# Supply.net
KiCad netlist of a schematic drawn in Altium Designer
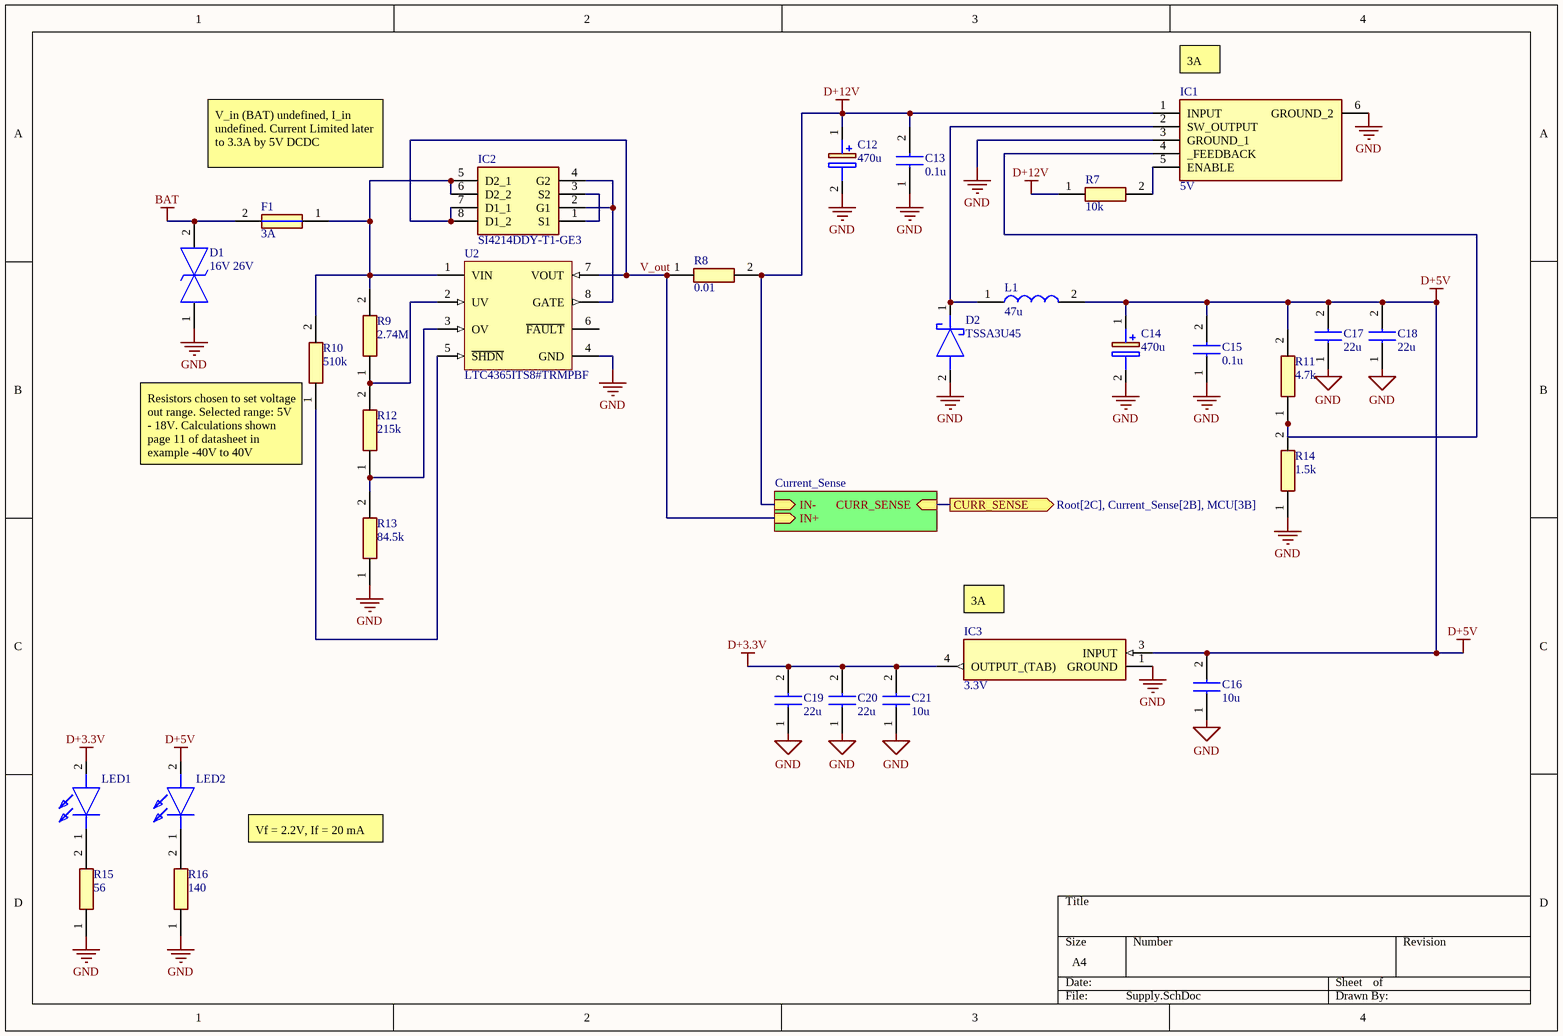
[diagram p0: Supply.SchDoc]

(export (version "E")
  (design (tool "Eeschema 10.0.6"))
  (components
    (comp (ref "C12")
      (value "470u")
      (footprint "SamacSys:CAPAE1030X1080N")
      (description "UWT1E471MNL1GS")
      (fields (field (name "MOUSER PART NUMBER") "647-UWT1E471MNL1S"))
      (libsource (lib "*") (part "UWT1E471MNL1GS"))
    )
    (comp (ref "C13")
      (value "0.1u")
      (footprint "SamacSys:CAPC1608X90N")
      (description "CC0603KRX7R8BB104")
      (fields (field (name "MOUSER PART NUMBER") "603-CC603KRX7R8BB104"))
      (libsource (lib "*") (part "CC0603KRX7R8BB104"))
    )
    (comp (ref "C14")
      (value "470u")
      (footprint "SamacSys:CAPAE1030X1080N")
      (description "UWT1E471MNL1GS")
      (fields (field (name "MOUSER PART NUMBER") "647-UWT1E471MNL1S"))
      (libsource (lib "*") (part "UWT1E471MNL1GS"))
    )
    (comp (ref "C15")
      (value "0.1u")
      (footprint "SamacSys:CAPC1608X90N")
      (description "CC0603KRX7R8BB104")
      (fields (field (name "MOUSER PART NUMBER") "603-CC603KRX7R8BB104"))
      (libsource (lib "*") (part "CC0603KRX7R8BB104"))
    )
    (comp (ref "C16")
      (value "10u")
      (footprint "SamacSys:GRM18x")
      (description "GRM188R61A106ME69D")
      (fields (field (name "MOUSER PART NUMBER") "81-GRM188R61A106ME9D"))
      (libsource (lib "*") (part "GRM188R61A106ME69D"))
    )
    (comp (ref "C17")
      (value "22u")
      (footprint "SamacSys:CAPC2012X95N")
      (description "GRM219R61A226MEA0D")
      (fields (field (name "MOUSER PART NUMBER") "81-GRM219R61A226ME0D"))
      (libsource (lib "*") (part "GRM219R61A226MEA0D"))
    )
    (comp (ref "C18")
      (value "22u")
      (footprint "SamacSys:CAPC2012X95N")
      (description "GRM219R61A226MEA0D")
      (fields (field (name "MOUSER PART NUMBER") "81-GRM219R61A226ME0D"))
      (libsource (lib "*") (part "GRM219R61A226MEA0D"))
    )
    (comp (ref "C19")
      (value "22u")
      (footprint "SamacSys:CAPC2012X95N")
      (description "GRM219R61A226MEA0D")
      (fields (field (name "MOUSER PART NUMBER") "81-GRM219R61A226ME0D"))
      (libsource (lib "*") (part "GRM219R61A226MEA0D"))
    )
    (comp (ref "C20")
      (value "22u")
      (footprint "SamacSys:CAPC2012X95N")
      (description "GRM219R61A226MEA0D")
      (fields (field (name "MOUSER PART NUMBER") "81-GRM219R61A226ME0D"))
      (libsource (lib "*") (part "GRM219R61A226MEA0D"))
    )
    (comp (ref "C21")
      (value "10u")
      (footprint "SamacSys:GRM18x")
      (description "GRM188R61A106ME69D")
      (fields (field (name "MOUSER PART NUMBER") "81-GRM188R61A106ME9D"))
      (libsource (lib "*") (part "GRM188R61A106ME69D"))
    )
    (comp (ref "D1")
      (value "16V 26V")
      (footprint "SamacSys:DIONM5226X240N")
      (description "SMAJ16CA-13-F")
      (fields (field (name "MOUSER PART NUMBER") "621-SMAJ16CA-13-F"))
      (libsource (lib "*") (part "SMAJ16CA-13-F"))
    )
    (comp (ref "D2")
      (value "TSSA3U45")
      (footprint "SamacSys:DIOM5126X250N")
      (description "Schottky Diode")
      (fields (field (name "MOUSER PART NUMBER") "821-TSSA3U45"))
      (libsource (lib "*") (part "TSSA3U45"))
    )
    (comp (ref "F1")
      (value "3A")
      (footprint "SamacSys:FUSC3216X83N")
      (description "0685T3000-01")
      (libsource (lib "*") (part "0685T3000-01"))
    )
    (comp (ref "IC1")
      (value "5V")
      (footprint "SamacSys:TS2596CM550RNG")
      (description "TS2596CM550_RNG")
      (fields
        (field (name "MANUFACTURER_PART_NUMBER") "TS2596CM550 RNG")
        (field (name "MOUSER PART NUMBER") "821-TS2596CM550RNG")
      )
      (libsource (lib "*") (part "TS2596CM550_RNG"))
    )
    (comp (ref "IC2")
      (value "SI4214DDY-T1-GE3")
      (footprint "SamacSys:SOIC127P600X175-8N")
      (description "Integrated Circuit")
      (fields (field (name "MOUSER PART NUMBER") "781-SI4214DDY-GE3"))
      (libsource (lib "*") (part "SI4214DDY-T1-GE3"))
    )
    (comp (ref "IC3")
      (value "3.3V")
      (footprint "SamacSys:TO254P1542X460-3N")
      (description "LD1085D2M33R")
      (fields (field (name "MOUSER PART NUMBER") "511-LD1085D2M33-TR"))
      (libsource (lib "*") (part "LD1085D2M33R"))
    )
    (comp (ref "L1")
      (value "47u")
      (footprint "SamacSys:104CDMCCDS470MC")
      (description "104CDMCCDS-470MC")
      (fields (field (name "MOUSER PART NUMBER") "851-104CDMCCDS-470MC"))
      (libsource (lib "*") (part "104CDMCCDS-470MC"))
    )
    (comp (ref "LED1")
      (value "SML-D12P8WT86C")
      (footprint "SamacSys:LEDM1620X150N")
      (description "LED")
      (fields (field (name "MOUSER PART NUMBER") "755-SML-D12P8WT86C"))
      (libsource (lib "*") (part "SML-D12P8WT86C"))
    )
    (comp (ref "LED2")
      (value "SML-D12P8WT86C")
      (footprint "SamacSys:LEDM1620X150N")
      (description "LED")
      (fields (field (name "MOUSER PART NUMBER") "755-SML-D12P8WT86C"))
      (libsource (lib "*") (part "SML-D12P8WT86C"))
    )
    (comp (ref "R7")
      (value "10k")
      (footprint "SamacSys:RESC1608X55N")
      (description "RC0603FR0710KL")
      (libsource (lib "*") (part "RC0603FR0710KL"))
    )
    (comp (ref "R8")
      (value "0.01")
      (footprint "SamacSys:CSS0603FT10L0")
      (description "CSS0603FT10L0")
      (fields (field (name "MOUSER PART NUMBER") "708-CSS0603FT10L0"))
      (libsource (lib "*") (part "CSS0603FT10L0"))
    )
    (comp (ref "R9")
      (value "2.74M")
      (footprint "SamacSys:RESC1608X50N")
      (description "CRCW06032M74FKEA")
      (fields (field (name "MOUSER PART NUMBER") "71-CRCW0603-2.74M-E3"))
      (libsource (lib "*") (part "CRCW06032M74FKEA"))
    )
    (comp (ref "R10")
      (value "510k")
      (footprint "SamacSys:RESC1608X55N")
      (description "RC0603JR-07510KL")
      (fields (field (name "MOUSER PART NUMBER") "603-RC0603JR-07510KL"))
      (libsource (lib "*") (part "RC0603JR-07510KL"))
    )
    (comp (ref "R11")
      (value "4.7k")
      (footprint "SamacSys:RESC1608X55N")
      (description "RC0603FR-074K7L")
      (fields (field (name "MOUSER PART NUMBER") "603-RC0603FR-074K7L"))
      (libsource (lib "*") (part "RC0603FR-074K7L"))
    )
    (comp (ref "R12")
      (value "215k")
      (footprint "SamacSys:RESC1608X55N")
      (description "ERJ-3EKF2153V")
      (fields (field (name "MOUSER PART NUMBER") "667-ERJ-3EKF2153V"))
      (libsource (lib "*") (part "ERJ-3EKF2153V"))
    )
    (comp (ref "R13")
      (value "84.5k")
      (footprint "SamacSys:RESC1608X55N")
      (description "RC0603FR-0784K5L")
      (fields (field (name "MOUSER PART NUMBER") "603-RC0603FR-0784K5L"))
      (libsource (lib "*") (part "RC0603FR-0784K5L"))
    )
    (comp (ref "R14")
      (value "1.5k")
      (footprint "SamacSys:RESC1608X55N")
      (description "RC0603FR-071K5L")
      (fields (field (name "MOUSER PART NUMBER") "603-RC0603FR-071K5L"))
      (libsource (lib "*") (part "RC0603FR-071K5L"))
    )
    (comp (ref "R15")
      (value "56")
      (footprint "SamacSys:RESC2012X60N")
      (description "RC0805FR-0756RL")
      (fields (field (name "MOUSER PART NUMBER") "603-RC0805FR-0756RL"))
      (libsource (lib "*") (part "RC0805FR-0756RL"))
    )
    (comp (ref "R16")
      (value "140")
      (footprint "SamacSys:RESC2012X60N")
      (description "RC0805FR-07140RL")
      (fields (field (name "MOUSER PART NUMBER") "603-RC0805FR-07140RL"))
      (libsource (lib "*") (part "RC0805FR-07140RL"))
    )
    (comp (ref "U2")
      (value "LTC4365ITS8#TRMPBF")
      (footprint "LT-TS8-8-TSOT-23_V")
      (fields (field (name "MANUFACTURER") "Linear Technology"))
      (libsource (lib "Altium Content Vault") (part "LT-LTC4365-TS8-8"))
    )
  )
  (nets
    (net (code "2") (name "/V_out") (class "Default")
      (node (ref "IC2") (pin "7") (pinfunction "D1_1_7") (pintype "passive"))
      (node (ref "IC2") (pin "8") (pinfunction "D1_2_8") (pintype "passive"))
      (node (ref "R8") (pin "1") (pinfunction "1_1") (pintype "passive"))
      (node (ref "U2") (pin "7") (pinfunction "VOUT_7") (pintype "input"))
    )
    (net (code "3") (name "BAT") (class "Default")
      (node (ref "D1") (pin "2") (pinfunction "2_2") (pintype "passive"))
      (node (ref "F1") (pin "2") (pinfunction "2_2") (pintype "passive"))
    )
    (net (code "4") (name "D+3.3V") (class "Default")
      (node (ref "C19") (pin "2") (pinfunction "2_2") (pintype "passive"))
      (node (ref "C20") (pin "2") (pinfunction "2_2") (pintype "passive"))
      (node (ref "C21") (pin "2") (pinfunction "2_2") (pintype "passive"))
      (node (ref "IC3") (pin "4") (pinfunction "OUTPUT_(TAB)_4") (pintype "output"))
      (node (ref "LED1") (pin "2") (pinfunction "A_2") (pintype "passive"))
    )
    (net (code "5") (name "D+5V") (class "Default")
      (node (ref "C14") (pin "1") (pinfunction "+_1") (pintype "passive"))
      (node (ref "C15") (pin "2") (pinfunction "2_2") (pintype "passive"))
      (node (ref "C16") (pin "2") (pinfunction "2_2") (pintype "passive"))
      (node (ref "C17") (pin "2") (pinfunction "2_2") (pintype "passive"))
      (node (ref "C18") (pin "2") (pinfunction "2_2") (pintype "passive"))
      (node (ref "IC3") (pin "3") (pinfunction "INPUT_3") (pintype "input"))
      (node (ref "L1") (pin "2") (pinfunction "2_2") (pintype "passive"))
      (node (ref "LED2") (pin "2") (pinfunction "A_2") (pintype "passive"))
      (node (ref "R11") (pin "2") (pinfunction "2_2") (pintype "passive"))
    )
    (net (code "6") (name "D+12V") (class "Default")
      (node (ref "C12") (pin "1") (pinfunction "+_1") (pintype "passive"))
      (node (ref "C13") (pin "2") (pinfunction "2_2") (pintype "passive"))
      (node (ref "IC1") (pin "1") (pinfunction "INPUT_1") (pintype "passive"))
      (node (ref "R7") (pin "1") (pinfunction "1_1") (pintype "passive"))
      (node (ref "R8") (pin "2") (pinfunction "2_2") (pintype "passive"))
    )
    (net (code "7") (name "GND") (class "Default")
      (node (ref "C12") (pin "2") (pinfunction "-_2") (pintype "passive"))
      (node (ref "C13") (pin "1") (pinfunction "1_1") (pintype "passive"))
      (node (ref "C14") (pin "2") (pinfunction "-_2") (pintype "passive"))
      (node (ref "C15") (pin "1") (pinfunction "1_1") (pintype "passive"))
      (node (ref "C16") (pin "1") (pinfunction "1_1") (pintype "passive"))
      (node (ref "C17") (pin "1") (pinfunction "1_1") (pintype "passive"))
      (node (ref "C18") (pin "1") (pinfunction "1_1") (pintype "passive"))
      (node (ref "C19") (pin "1") (pinfunction "1_1") (pintype "passive"))
      (node (ref "C20") (pin "1") (pinfunction "1_1") (pintype "passive"))
      (node (ref "C21") (pin "1") (pinfunction "1_1") (pintype "passive"))
      (node (ref "D1") (pin "1") (pinfunction "1_1") (pintype "passive"))
      (node (ref "D2") (pin "2") (pinfunction "A_2") (pintype "passive"))
      (node (ref "IC1") (pin "3") (pinfunction "GROUND_1_3") (pintype "passive"))
      (node (ref "IC1") (pin "6") (pinfunction "GROUND_2_6") (pintype "passive"))
      (node (ref "IC3") (pin "1") (pinfunction "GROUND_1") (pintype "passive"))
      (node (ref "R13") (pin "1") (pinfunction "1_1") (pintype "passive"))
      (node (ref "R14") (pin "1") (pinfunction "1_1") (pintype "passive"))
      (node (ref "R15") (pin "1") (pinfunction "1_1") (pintype "passive"))
      (node (ref "R16") (pin "1") (pinfunction "1_1") (pintype "passive"))
      (node (ref "U2") (pin "4") (pinfunction "GND_4") (pintype "power_in"))
    )
    (net (code "8") (name "Net-(D2-K)") (class "Default")
      (node (ref "D2") (pin "1") (pinfunction "K_1") (pintype "passive"))
      (node (ref "IC1") (pin "2") (pinfunction "SW_OUTPUT_2") (pintype "passive"))
      (node (ref "L1") (pin "1") (pinfunction "1_1") (pintype "passive"))
    )
    (net (code "9") (name "Net-(IC1-ENABLE)") (class "Default")
      (node (ref "IC1") (pin "5") (pinfunction "ENABLE_5") (pintype "passive"))
      (node (ref "R7") (pin "2") (pinfunction "2_2") (pintype "passive"))
    )
    (net (code "10") (name "Net-(IC1-_FEEDBACK)") (class "Default")
      (node (ref "IC1") (pin "4") (pinfunction "_FEEDBACK_4") (pintype "passive"))
      (node (ref "R11") (pin "1") (pinfunction "1_1") (pintype "passive"))
      (node (ref "R14") (pin "2") (pinfunction "2_2") (pintype "passive"))
    )
    (net (code "11") (name "Net-(IC2-D2_1)") (class "Default")
      (node (ref "F1") (pin "1") (pinfunction "1_1") (pintype "passive"))
      (node (ref "IC2") (pin "5") (pinfunction "D2_1_5") (pintype "passive"))
      (node (ref "IC2") (pin "6") (pinfunction "D2_2_6") (pintype "passive"))
      (node (ref "R10") (pin "2") (pinfunction "2_2") (pintype "passive"))
      (node (ref "R9") (pin "2") (pinfunction "2_2") (pintype "passive"))
      (node (ref "U2") (pin "1") (pinfunction "VIN_1") (pintype "power_in"))
    )
    (net (code "12") (name "Net-(IC2-G1)") (class "Default")
      (node (ref "IC2") (pin "2") (pinfunction "G1_2") (pintype "passive"))
      (node (ref "IC2") (pin "4") (pinfunction "G2_4") (pintype "passive"))
      (node (ref "U2") (pin "8") (pinfunction "GATE_8") (pintype "output"))
    )
    (net (code "13") (name "Net-(IC2-S1)") (class "Default")
      (node (ref "IC2") (pin "1") (pinfunction "S1_1") (pintype "passive"))
      (node (ref "IC2") (pin "3") (pinfunction "S2_3") (pintype "passive"))
    )
    (net (code "14") (name "Net-(LED1-K)") (class "Default")
      (node (ref "LED1") (pin "1") (pinfunction "K_1") (pintype "passive"))
      (node (ref "R15") (pin "2") (pinfunction "2_2") (pintype "passive"))
    )
    (net (code "15") (name "Net-(LED2-K)") (class "Default")
      (node (ref "LED2") (pin "1") (pinfunction "K_1") (pintype "passive"))
      (node (ref "R16") (pin "2") (pinfunction "2_2") (pintype "passive"))
    )
    (net (code "16") (name "Net-(U2-OV)") (class "Default")
      (node (ref "R12") (pin "1") (pinfunction "1_1") (pintype "passive"))
      (node (ref "R13") (pin "2") (pinfunction "2_2") (pintype "passive"))
      (node (ref "U2") (pin "3") (pinfunction "OV_3") (pintype "input"))
    )
    (net (code "17") (name "Net-(U2-UV)") (class "Default")
      (node (ref "R12") (pin "2") (pinfunction "2_2") (pintype "passive"))
      (node (ref "R9") (pin "1") (pinfunction "1_1") (pintype "passive"))
      (node (ref "U2") (pin "2") (pinfunction "UV_2") (pintype "input"))
    )
    (net (code "18") (name "Net-(U2-~{SHDN})") (class "Default")
      (node (ref "R10") (pin "1") (pinfunction "1_1") (pintype "passive"))
      (node (ref "U2") (pin "5") (pinfunction "~{SHDN}_5") (pintype "input"))
    )
    (net (code "19") (name "unconnected-(U2-~{FAULT}-Pad6)") (class "Default")
      (node (ref "U2") (pin "6") (pinfunction "~{FAULT}_6") (pintype "open_collector"))
    )
  )
)
